# main.net
KiCad netlist of a schematic drawn in EAGLE
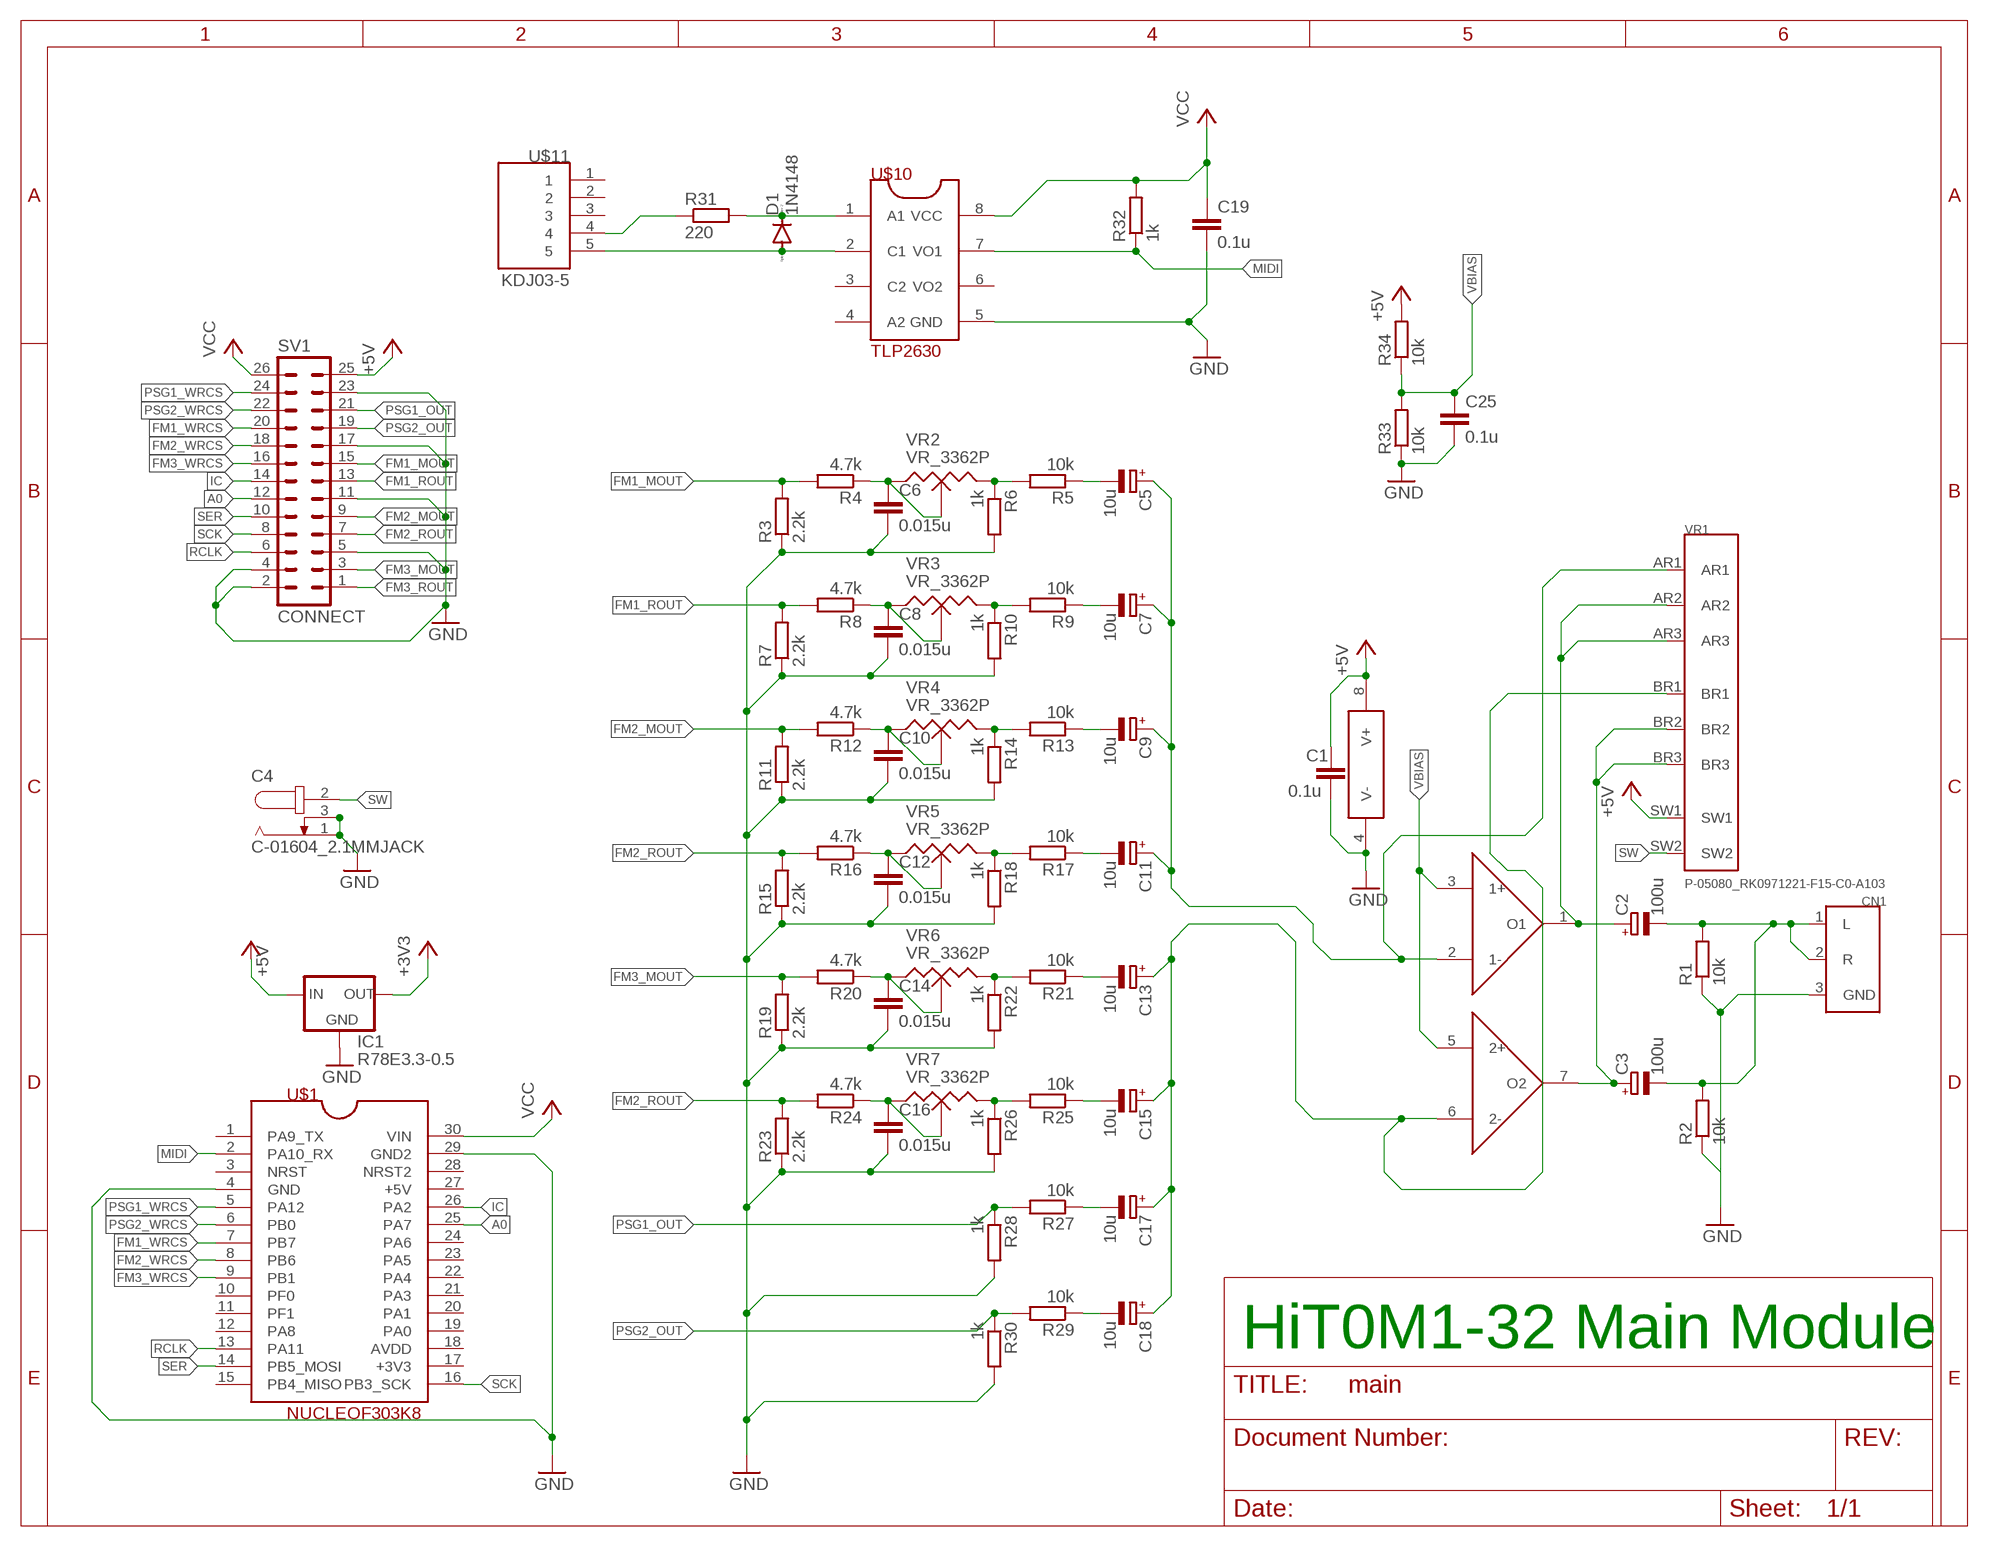
[diagram p0: schematic, sheet 1]

(export (version "E")
  (design (tool "Eeschema 10.0.6"))
  (components
    (comp (ref "C1")
      (value "0.1u")
      (footprint "eagle-import:C025-025X050")
      (libsource (lib "eagle-import") (part "C-EU025-025X050"))
    )
    (comp (ref "C2")
      (value "100u")
      (footprint "eagle-import:E2,5-6E")
      (libsource (lib "eagle-import") (part "CPOL-EUE2,5-6E"))
    )
    (comp (ref "C3")
      (value "100u")
      (footprint "eagle-import:E2,5-6E")
      (libsource (lib "eagle-import") (part "CPOL-EUE2,5-6E"))
    )
    (comp (ref "C4")
      (value "C-01604_2.1MMJACK")
      (footprint "eagle-import:2.1MMJACK")
      (libsource (lib "eagle-import") (part "C-01604_2.1MMJACK"))
    )
    (comp (ref "C5")
      (value "10u")
      (footprint "eagle-import:E2,5-6E")
      (libsource (lib "eagle-import") (part "CPOL-EUE2,5-6E"))
    )
    (comp (ref "C6")
      (value "0.015u")
      (footprint "eagle-import:C050-025X075")
      (libsource (lib "eagle-import") (part "C-EU050-025X075"))
    )
    (comp (ref "C7")
      (value "10u")
      (footprint "eagle-import:E2,5-6E")
      (libsource (lib "eagle-import") (part "CPOL-EUE2,5-6E"))
    )
    (comp (ref "C8")
      (value "0.015u")
      (footprint "eagle-import:C050-025X075")
      (libsource (lib "eagle-import") (part "C-EU050-025X075"))
    )
    (comp (ref "C9")
      (value "10u")
      (footprint "eagle-import:E2,5-6E")
      (libsource (lib "eagle-import") (part "CPOL-EUE2,5-6E"))
    )
    (comp (ref "C10")
      (value "0.015u")
      (footprint "eagle-import:C050-025X075")
      (libsource (lib "eagle-import") (part "C-EU050-025X075"))
    )
    (comp (ref "C11")
      (value "10u")
      (footprint "eagle-import:E2,5-6E")
      (libsource (lib "eagle-import") (part "CPOL-EUE2,5-6E"))
    )
    (comp (ref "C12")
      (value "0.015u")
      (footprint "eagle-import:C050-025X075")
      (libsource (lib "eagle-import") (part "C-EU050-025X075"))
    )
    (comp (ref "C13")
      (value "10u")
      (footprint "eagle-import:E2,5-6E")
      (libsource (lib "eagle-import") (part "CPOL-EUE2,5-6E"))
    )
    (comp (ref "C14")
      (value "0.015u")
      (footprint "eagle-import:C050-025X075")
      (libsource (lib "eagle-import") (part "C-EU050-025X075"))
    )
    (comp (ref "C15")
      (value "10u")
      (footprint "eagle-import:E2,5-6E")
      (libsource (lib "eagle-import") (part "CPOL-EUE2,5-6E"))
    )
    (comp (ref "C16")
      (value "0.015u")
      (footprint "eagle-import:C050-025X075")
      (libsource (lib "eagle-import") (part "C-EU050-025X075"))
    )
    (comp (ref "C17")
      (value "10u")
      (footprint "eagle-import:E2,5-6E")
      (libsource (lib "eagle-import") (part "CPOL-EUE2,5-6E"))
    )
    (comp (ref "C18")
      (value "10u")
      (footprint "eagle-import:E2,5-6E")
      (libsource (lib "eagle-import") (part "CPOL-EUE2,5-6E"))
    )
    (comp (ref "C19")
      (value "0.1u")
      (footprint "eagle-import:C025-025X050")
      (libsource (lib "eagle-import") (part "C-EU025-025X050"))
    )
    (comp (ref "C25")
      (value "0.1u")
      (footprint "eagle-import:C025-025X050")
      (libsource (lib "eagle-import") (part "C-EU025-025X050"))
    )
    (comp (ref "CN1")
      (value "C-08958_MJ-352W-0")
      (footprint "eagle-import:MJ-352W-0")
      (libsource (lib "eagle-import") (part "C-08958_MJ-352W-0"))
    )
    (comp (ref "D1")
      (value "1N4148")
      (footprint "eagle-import:DO35-7")
      (libsource (lib "eagle-import") (part "1N4148DO35-7"))
    )
    (comp (ref "IC1")
      (value "R78E3.3-0.5")
      (footprint "eagle-import:78XXS")
      (libsource (lib "eagle-import") (part "78XXS"))
    )
    (comp (ref "R1")
      (value "10k")
      (footprint "eagle-import:0204_7")
      (libsource (lib "eagle-import") (part "R-EU_0204/7"))
    )
    (comp (ref "R2")
      (value "10k")
      (footprint "eagle-import:0204_7")
      (libsource (lib "eagle-import") (part "R-EU_0204/7"))
    )
    (comp (ref "R3")
      (value "2.2k")
      (footprint "eagle-import:0204_7")
      (libsource (lib "eagle-import") (part "R-EU_0204/7"))
    )
    (comp (ref "R4")
      (value "4.7k")
      (footprint "eagle-import:0204_7")
      (libsource (lib "eagle-import") (part "R-EU_0204/7"))
    )
    (comp (ref "R5")
      (value "10k")
      (footprint "eagle-import:0204_7")
      (libsource (lib "eagle-import") (part "R-EU_0204/7"))
    )
    (comp (ref "R6")
      (value "1k")
      (footprint "eagle-import:0204_7")
      (libsource (lib "eagle-import") (part "R-EU_0204/7"))
    )
    (comp (ref "R7")
      (value "2.2k")
      (footprint "eagle-import:0204_7")
      (libsource (lib "eagle-import") (part "R-EU_0204/7"))
    )
    (comp (ref "R8")
      (value "4.7k")
      (footprint "eagle-import:0204_7")
      (libsource (lib "eagle-import") (part "R-EU_0204/7"))
    )
    (comp (ref "R9")
      (value "10k")
      (footprint "eagle-import:0204_7")
      (libsource (lib "eagle-import") (part "R-EU_0204/7"))
    )
    (comp (ref "R10")
      (value "1k")
      (footprint "eagle-import:0204_7")
      (libsource (lib "eagle-import") (part "R-EU_0204/7"))
    )
    (comp (ref "R11")
      (value "2.2k")
      (footprint "eagle-import:0204_7")
      (libsource (lib "eagle-import") (part "R-EU_0204/7"))
    )
    (comp (ref "R12")
      (value "4.7k")
      (footprint "eagle-import:0204_7")
      (libsource (lib "eagle-import") (part "R-EU_0204/7"))
    )
    (comp (ref "R13")
      (value "10k")
      (footprint "eagle-import:0204_7")
      (libsource (lib "eagle-import") (part "R-EU_0204/7"))
    )
    (comp (ref "R14")
      (value "1k")
      (footprint "eagle-import:0204_7")
      (libsource (lib "eagle-import") (part "R-EU_0204/7"))
    )
    (comp (ref "R15")
      (value "2.2k")
      (footprint "eagle-import:0204_7")
      (libsource (lib "eagle-import") (part "R-EU_0204/7"))
    )
    (comp (ref "R16")
      (value "4.7k")
      (footprint "eagle-import:0204_7")
      (libsource (lib "eagle-import") (part "R-EU_0204/7"))
    )
    (comp (ref "R17")
      (value "10k")
      (footprint "eagle-import:0204_7")
      (libsource (lib "eagle-import") (part "R-EU_0204/7"))
    )
    (comp (ref "R18")
      (value "1k")
      (footprint "eagle-import:0204_7")
      (libsource (lib "eagle-import") (part "R-EU_0204/7"))
    )
    (comp (ref "R19")
      (value "2.2k")
      (footprint "eagle-import:0204_7")
      (libsource (lib "eagle-import") (part "R-EU_0204/7"))
    )
    (comp (ref "R20")
      (value "4.7k")
      (footprint "eagle-import:0204_7")
      (libsource (lib "eagle-import") (part "R-EU_0204/7"))
    )
    (comp (ref "R21")
      (value "10k")
      (footprint "eagle-import:0204_7")
      (libsource (lib "eagle-import") (part "R-EU_0204/7"))
    )
    (comp (ref "R22")
      (value "1k")
      (footprint "eagle-import:0204_7")
      (libsource (lib "eagle-import") (part "R-EU_0204/7"))
    )
    (comp (ref "R23")
      (value "2.2k")
      (footprint "eagle-import:0204_7")
      (libsource (lib "eagle-import") (part "R-EU_0204/7"))
    )
    (comp (ref "R24")
      (value "4.7k")
      (footprint "eagle-import:0204_7")
      (libsource (lib "eagle-import") (part "R-EU_0204/7"))
    )
    (comp (ref "R25")
      (value "10k")
      (footprint "eagle-import:0204_7")
      (libsource (lib "eagle-import") (part "R-EU_0204/7"))
    )
    (comp (ref "R26")
      (value "1k")
      (footprint "eagle-import:0204_7")
      (libsource (lib "eagle-import") (part "R-EU_0204/7"))
    )
    (comp (ref "R27")
      (value "10k")
      (footprint "eagle-import:0204_7")
      (libsource (lib "eagle-import") (part "R-EU_0204/7"))
    )
    (comp (ref "R28")
      (value "1k")
      (footprint "eagle-import:0204_7")
      (libsource (lib "eagle-import") (part "R-EU_0204/7"))
    )
    (comp (ref "R29")
      (value "10k")
      (footprint "eagle-import:0204_7")
      (libsource (lib "eagle-import") (part "R-EU_0204/7"))
    )
    (comp (ref "R30")
      (value "1k")
      (footprint "eagle-import:0204_7")
      (libsource (lib "eagle-import") (part "R-EU_0204/7"))
    )
    (comp (ref "R31")
      (value "220")
      (footprint "eagle-import:0204_7")
      (libsource (lib "eagle-import") (part "R-EU_0204/7"))
    )
    (comp (ref "R32")
      (value "1k")
      (footprint "eagle-import:0204_7")
      (libsource (lib "eagle-import") (part "R-EU_0204/7"))
    )
    (comp (ref "R33")
      (value "10k")
      (footprint "eagle-import:0204_7")
      (libsource (lib "eagle-import") (part "R-EU_0204/7"))
    )
    (comp (ref "R34")
      (value "10k")
      (footprint "eagle-import:0204_7")
      (libsource (lib "eagle-import") (part "R-EU_0204/7"))
    )
    (comp (ref "SV1")
      (value "CONNECT")
      (footprint "eagle-import:MA13-2")
      (libsource (lib "eagle-import") (part "MA13-2"))
    )
    (comp (ref "U$1")
      (value "NUCLEOF303K8")
      (footprint "eagle-import:NUCLEOF303K8")
      (libsource (lib "eagle-import") (part "NUCLEOF303K8"))
    )
    (comp (ref "U$2")
      (value "NJM2114")
      (footprint "eagle-import:DIL08")
      (libsource (lib "eagle-import") (part "NJM2114"))
    )
    (comp (ref "U$10")
      (value "TLP2630")
      (footprint "eagle-import:DIL08")
      (libsource (lib "eagle-import") (part "TLP2630TLP2630"))
    )
    (comp (ref "U$11")
      (value "KDJ03-5")
      (footprint "eagle-import:KDJ03-5")
      (libsource (lib "eagle-import") (part "KDJ03-5"))
    )
    (comp (ref "VR1")
      (value "P-05080_RK0971221-F15-C0-A103")
      (footprint "eagle-import:RK0971221-F15-C0-A103")
      (libsource (lib "eagle-import") (part "P-05080_RK0971221-F15-C0-A103"))
    )
    (comp (ref "VR2")
      (value "VR_3362P")
      (footprint "eagle-import:VR_3362P")
      (libsource (lib "eagle-import") (part "P-03277_VR_3362P"))
    )
    (comp (ref "VR3")
      (value "VR_3362P")
      (footprint "eagle-import:VR_3362P")
      (libsource (lib "eagle-import") (part "P-03277_VR_3362P"))
    )
    (comp (ref "VR4")
      (value "VR_3362P")
      (footprint "eagle-import:VR_3362P")
      (libsource (lib "eagle-import") (part "P-03277_VR_3362P"))
    )
    (comp (ref "VR5")
      (value "VR_3362P")
      (footprint "eagle-import:VR_3362P")
      (libsource (lib "eagle-import") (part "P-03277_VR_3362P"))
    )
    (comp (ref "VR6")
      (value "VR_3362P")
      (footprint "eagle-import:VR_3362P")
      (libsource (lib "eagle-import") (part "P-03277_VR_3362P"))
    )
    (comp (ref "VR7")
      (value "VR_3362P")
      (footprint "eagle-import:VR_3362P")
      (libsource (lib "eagle-import") (part "P-03277_VR_3362P"))
    )
  )
  (nets
    (net (code "1") (name "+3V3") (class "Default")
      (node (ref "IC1") (pin "OUT") (pinfunction "OUT_OUT") (pintype "passive"))
    )
    (net (code "2") (name "+5V") (class "Default")
      (node (ref "C1") (pin "1") (pinfunction "1_1") (pintype "passive"))
      (node (ref "IC1") (pin "IN") (pinfunction "IN_IN") (pintype "input"))
      (node (ref "R34") (pin "2") (pinfunction "2_2") (pintype "passive"))
      (node (ref "SV1") (pin "25") (pinfunction "25_25") (pintype "passive"))
      (node (ref "U$2") (pin "8") (pinfunction "V+_8") (pintype "bidirectional"))
      (node (ref "VR1") (pin "SW1") (pinfunction "SW1_SW1") (pintype "bidirectional"))
    )
    (net (code "3") (name "A0") (class "Default")
      (node (ref "SV1") (pin "12") (pinfunction "12_12") (pintype "passive"))
      (node (ref "U$1") (pin "25") (pinfunction "PA7_25") (pintype "bidirectional"))
    )
    (net (code "4") (name "FM1_MOUT") (class "Default")
      (node (ref "R3") (pin "2") (pinfunction "2_2") (pintype "passive"))
      (node (ref "R4") (pin "2") (pinfunction "2_2") (pintype "passive"))
      (node (ref "SV1") (pin "15") (pinfunction "15_15") (pintype "passive"))
    )
    (net (code "5") (name "FM1_ROUT") (class "Default")
      (node (ref "R7") (pin "2") (pinfunction "2_2") (pintype "passive"))
      (node (ref "R8") (pin "2") (pinfunction "2_2") (pintype "passive"))
      (node (ref "SV1") (pin "13") (pinfunction "13_13") (pintype "passive"))
    )
    (net (code "6") (name "FM1_WRCS") (class "Default")
      (node (ref "SV1") (pin "20") (pinfunction "20_20") (pintype "passive"))
      (node (ref "U$1") (pin "7") (pinfunction "PB7_7") (pintype "bidirectional"))
    )
    (net (code "7") (name "FM2_MOUT") (class "Default")
      (node (ref "R11") (pin "2") (pinfunction "2_2") (pintype "passive"))
      (node (ref "R12") (pin "2") (pinfunction "2_2") (pintype "passive"))
      (node (ref "SV1") (pin "9") (pinfunction "9_9") (pintype "passive"))
    )
    (net (code "8") (name "FM2_ROUT") (class "Default")
      (node (ref "R15") (pin "2") (pinfunction "2_2") (pintype "passive"))
      (node (ref "R16") (pin "2") (pinfunction "2_2") (pintype "passive"))
      (node (ref "R23") (pin "2") (pinfunction "2_2") (pintype "passive"))
      (node (ref "R24") (pin "2") (pinfunction "2_2") (pintype "passive"))
      (node (ref "SV1") (pin "7") (pinfunction "7_7") (pintype "passive"))
    )
    (net (code "9") (name "FM2_WRCS") (class "Default")
      (node (ref "SV1") (pin "18") (pinfunction "18_18") (pintype "passive"))
      (node (ref "U$1") (pin "8") (pinfunction "PB6_8") (pintype "bidirectional"))
    )
    (net (code "10") (name "FM3_MOUT") (class "Default")
      (node (ref "R19") (pin "2") (pinfunction "2_2") (pintype "passive"))
      (node (ref "R20") (pin "2") (pinfunction "2_2") (pintype "passive"))
      (node (ref "SV1") (pin "3") (pinfunction "3_3") (pintype "passive"))
    )
    (net (code "11") (name "FM3_ROUT") (class "Default")
      (node (ref "SV1") (pin "1") (pinfunction "1_1") (pintype "passive"))
    )
    (net (code "12") (name "FM3_WRCS") (class "Default")
      (node (ref "SV1") (pin "16") (pinfunction "16_16") (pintype "passive"))
      (node (ref "U$1") (pin "9") (pinfunction "PB1_9") (pintype "bidirectional"))
    )
    (net (code "13") (name "GND") (class "Default")
      (node (ref "C1") (pin "2") (pinfunction "2_2") (pintype "passive"))
      (node (ref "C10") (pin "2") (pinfunction "2_2") (pintype "passive"))
      (node (ref "C12") (pin "2") (pinfunction "2_2") (pintype "passive"))
      (node (ref "C14") (pin "2") (pinfunction "2_2") (pintype "passive"))
      (node (ref "C16") (pin "2") (pinfunction "2_2") (pintype "passive"))
      (node (ref "C19") (pin "2") (pinfunction "2_2") (pintype "passive"))
      (node (ref "C25") (pin "2") (pinfunction "2_2") (pintype "passive"))
      (node (ref "C4") (pin "1") (pinfunction "GND_1") (pintype "passive"))
      (node (ref "C4") (pin "3") (pinfunction "S_3") (pintype "passive"))
      (node (ref "C6") (pin "2") (pinfunction "2_2") (pintype "passive"))
      (node (ref "C8") (pin "2") (pinfunction "2_2") (pintype "passive"))
      (node (ref "CN1") (pin "3") (pinfunction "GND_3") (pintype "bidirectional"))
      (node (ref "IC1") (pin "GND") (pinfunction "GND_GND") (pintype "input"))
      (node (ref "R1") (pin "1") (pinfunction "1_1") (pintype "passive"))
      (node (ref "R10") (pin "2") (pinfunction "2_2") (pintype "passive"))
      (node (ref "R11") (pin "1") (pinfunction "1_1") (pintype "passive"))
      (node (ref "R14") (pin "2") (pinfunction "2_2") (pintype "passive"))
      (node (ref "R15") (pin "1") (pinfunction "1_1") (pintype "passive"))
      (node (ref "R18") (pin "2") (pinfunction "2_2") (pintype "passive"))
      (node (ref "R19") (pin "1") (pinfunction "1_1") (pintype "passive"))
      (node (ref "R22") (pin "2") (pinfunction "2_2") (pintype "passive"))
      (node (ref "R23") (pin "1") (pinfunction "1_1") (pintype "passive"))
      (node (ref "R26") (pin "2") (pinfunction "2_2") (pintype "passive"))
      (node (ref "R28") (pin "2") (pinfunction "2_2") (pintype "passive"))
      (node (ref "R3") (pin "1") (pinfunction "1_1") (pintype "passive"))
      (node (ref "R30") (pin "2") (pinfunction "2_2") (pintype "passive"))
      (node (ref "R33") (pin "1") (pinfunction "1_1") (pintype "passive"))
      (node (ref "R6") (pin "2") (pinfunction "2_2") (pintype "passive"))
      (node (ref "R7") (pin "1") (pinfunction "1_1") (pintype "passive"))
      (node (ref "SV1") (pin "11") (pinfunction "11_11") (pintype "passive"))
      (node (ref "SV1") (pin "17") (pinfunction "17_17") (pintype "passive"))
      (node (ref "SV1") (pin "2") (pinfunction "2_2") (pintype "passive"))
      (node (ref "SV1") (pin "23") (pinfunction "23_23") (pintype "passive"))
      (node (ref "SV1") (pin "4") (pinfunction "4_4") (pintype "passive"))
      (node (ref "SV1") (pin "5") (pinfunction "5_5") (pintype "passive"))
      (node (ref "U$1") (pin "29") (pinfunction "GND2_29") (pintype "bidirectional"))
      (node (ref "U$1") (pin "4") (pinfunction "GND_4") (pintype "bidirectional"))
      (node (ref "U$10") (pin "5") (pinfunction "GND_5") (pintype "bidirectional"))
      (node (ref "U$2") (pin "4") (pinfunction "V-_4") (pintype "bidirectional"))
    )
    (net (code "14") (name "IC") (class "Default")
      (node (ref "SV1") (pin "14") (pinfunction "14_14") (pintype "passive"))
      (node (ref "U$1") (pin "26") (pinfunction "PA2_26") (pintype "bidirectional"))
    )
    (net (code "15") (name "MIDI") (class "Default")
      (node (ref "R32") (pin "1") (pinfunction "1_1") (pintype "passive"))
      (node (ref "U$1") (pin "2") (pinfunction "PA10_RX_2") (pintype "bidirectional"))
      (node (ref "U$10") (pin "7") (pinfunction "VO1_7") (pintype "bidirectional"))
    )
    (net (code "16") (name "Net-(C5-Pad-)") (class "Default")
      (node (ref "C5") (pin "-") (pinfunction "-_-") (pintype "passive"))
      (node (ref "R5") (pin "1") (pinfunction "1_1") (pintype "passive"))
    )
    (net (code "17") (name "Net-(C6-Pad1)") (class "Default")
      (node (ref "C6") (pin "1") (pinfunction "1_1") (pintype "passive"))
      (node (ref "R4") (pin "1") (pinfunction "1_1") (pintype "passive"))
      (node (ref "VR2") (pin "1") (pinfunction "1_1") (pintype "bidirectional"))
      (node (ref "VR2") (pin "2") (pinfunction "2_2") (pintype "bidirectional"))
    )
    (net (code "18") (name "Net-(C7-Pad-)") (class "Default")
      (node (ref "C7") (pin "-") (pinfunction "-_-") (pintype "passive"))
      (node (ref "R9") (pin "1") (pinfunction "1_1") (pintype "passive"))
    )
    (net (code "19") (name "Net-(C8-Pad1)") (class "Default")
      (node (ref "C8") (pin "1") (pinfunction "1_1") (pintype "passive"))
      (node (ref "R8") (pin "1") (pinfunction "1_1") (pintype "passive"))
      (node (ref "VR3") (pin "1") (pinfunction "1_1") (pintype "bidirectional"))
      (node (ref "VR3") (pin "2") (pinfunction "2_2") (pintype "bidirectional"))
    )
    (net (code "20") (name "Net-(C9-Pad-)") (class "Default")
      (node (ref "C9") (pin "-") (pinfunction "-_-") (pintype "passive"))
      (node (ref "R13") (pin "1") (pinfunction "1_1") (pintype "passive"))
    )
    (net (code "21") (name "Net-(C10-Pad1)") (class "Default")
      (node (ref "C10") (pin "1") (pinfunction "1_1") (pintype "passive"))
      (node (ref "R12") (pin "1") (pinfunction "1_1") (pintype "passive"))
      (node (ref "VR4") (pin "1") (pinfunction "1_1") (pintype "bidirectional"))
      (node (ref "VR4") (pin "2") (pinfunction "2_2") (pintype "bidirectional"))
    )
    (net (code "22") (name "Net-(C11-Pad-)") (class "Default")
      (node (ref "C11") (pin "-") (pinfunction "-_-") (pintype "passive"))
      (node (ref "R17") (pin "1") (pinfunction "1_1") (pintype "passive"))
    )
    (net (code "23") (name "Net-(C12-Pad1)") (class "Default")
      (node (ref "C12") (pin "1") (pinfunction "1_1") (pintype "passive"))
      (node (ref "R16") (pin "1") (pinfunction "1_1") (pintype "passive"))
      (node (ref "VR5") (pin "1") (pinfunction "1_1") (pintype "bidirectional"))
      (node (ref "VR5") (pin "2") (pinfunction "2_2") (pintype "bidirectional"))
    )
    (net (code "24") (name "Net-(C13-Pad-)") (class "Default")
      (node (ref "C13") (pin "-") (pinfunction "-_-") (pintype "passive"))
      (node (ref "R21") (pin "1") (pinfunction "1_1") (pintype "passive"))
    )
    (net (code "25") (name "Net-(C14-Pad1)") (class "Default")
      (node (ref "C14") (pin "1") (pinfunction "1_1") (pintype "passive"))
      (node (ref "R20") (pin "1") (pinfunction "1_1") (pintype "passive"))
      (node (ref "VR6") (pin "1") (pinfunction "1_1") (pintype "bidirectional"))
      (node (ref "VR6") (pin "2") (pinfunction "2_2") (pintype "bidirectional"))
    )
    (net (code "26") (name "Net-(C15-Pad-)") (class "Default")
      (node (ref "C15") (pin "-") (pinfunction "-_-") (pintype "passive"))
      (node (ref "R25") (pin "1") (pinfunction "1_1") (pintype "passive"))
    )
    (net (code "27") (name "Net-(C16-Pad1)") (class "Default")
      (node (ref "C16") (pin "1") (pinfunction "1_1") (pintype "passive"))
      (node (ref "R24") (pin "1") (pinfunction "1_1") (pintype "passive"))
      (node (ref "VR7") (pin "1") (pinfunction "1_1") (pintype "bidirectional"))
      (node (ref "VR7") (pin "2") (pinfunction "2_2") (pintype "bidirectional"))
    )
    (net (code "28") (name "Net-(C17-Pad-)") (class "Default")
      (node (ref "C17") (pin "-") (pinfunction "-_-") (pintype "passive"))
      (node (ref "R27") (pin "1") (pinfunction "1_1") (pintype "passive"))
    )
    (net (code "29") (name "Net-(C18-Pad-)") (class "Default")
      (node (ref "C18") (pin "-") (pinfunction "-_-") (pintype "passive"))
      (node (ref "R29") (pin "1") (pinfunction "1_1") (pintype "passive"))
    )
    (net (code "30") (name "Net-(CN1-L)") (class "Default")
      (node (ref "C2") (pin "-") (pinfunction "-_-") (pintype "passive"))
      (node (ref "C3") (pin "-") (pinfunction "-_-") (pintype "passive"))
      (node (ref "CN1") (pin "1") (pinfunction "L_1") (pintype "bidirectional"))
      (node (ref "CN1") (pin "2") (pinfunction "R_2") (pintype "bidirectional"))
      (node (ref "R1") (pin "2") (pinfunction "2_2") (pintype "passive"))
      (node (ref "R2") (pin "2") (pinfunction "2_2") (pintype "passive"))
    )
    (net (code "31") (name "Net-(R5-Pad2)") (class "Default")
      (node (ref "R5") (pin "2") (pinfunction "2_2") (pintype "passive"))
      (node (ref "R6") (pin "1") (pinfunction "1_1") (pintype "passive"))
      (node (ref "VR2") (pin "3") (pinfunction "3_3") (pintype "bidirectional"))
    )
    (net (code "32") (name "Net-(R10-Pad1)") (class "Default")
      (node (ref "R10") (pin "1") (pinfunction "1_1") (pintype "passive"))
      (node (ref "R9") (pin "2") (pinfunction "2_2") (pintype "passive"))
      (node (ref "VR3") (pin "3") (pinfunction "3_3") (pintype "bidirectional"))
    )
    (net (code "33") (name "Net-(R13-Pad2)") (class "Default")
      (node (ref "R13") (pin "2") (pinfunction "2_2") (pintype "passive"))
      (node (ref "R14") (pin "1") (pinfunction "1_1") (pintype "passive"))
      (node (ref "VR4") (pin "3") (pinfunction "3_3") (pintype "bidirectional"))
    )
    (net (code "34") (name "Net-(R17-Pad2)") (class "Default")
      (node (ref "R17") (pin "2") (pinfunction "2_2") (pintype "passive"))
      (node (ref "R18") (pin "1") (pinfunction "1_1") (pintype "passive"))
      (node (ref "VR5") (pin "3") (pinfunction "3_3") (pintype "bidirectional"))
    )
    (net (code "35") (name "Net-(R21-Pad2)") (class "Default")
      (node (ref "R21") (pin "2") (pinfunction "2_2") (pintype "passive"))
      (node (ref "R22") (pin "1") (pinfunction "1_1") (pintype "passive"))
      (node (ref "VR6") (pin "3") (pinfunction "3_3") (pintype "bidirectional"))
    )
    (net (code "36") (name "Net-(R25-Pad2)") (class "Default")
      (node (ref "R25") (pin "2") (pinfunction "2_2") (pintype "passive"))
      (node (ref "R26") (pin "1") (pinfunction "1_1") (pintype "passive"))
      (node (ref "VR7") (pin "3") (pinfunction "3_3") (pintype "bidirectional"))
    )
    (net (code "37") (name "Net-(R31-Pad1)") (class "Default")
      (node (ref "R31") (pin "1") (pinfunction "1_1") (pintype "passive"))
      (node (ref "U$11") (pin "4") (pinfunction "4_4") (pintype "bidirectional"))
    )
    (net (code "38") (name "Net-(U$2-1-)") (class "Default")
      (node (ref "C11") (pin "+") (pinfunction "+_+") (pintype "passive"))
      (node (ref "C5") (pin "+") (pinfunction "+_+") (pintype "passive"))
      (node (ref "C7") (pin "+") (pinfunction "+_+") (pintype "passive"))
      (node (ref "C9") (pin "+") (pinfunction "+_+") (pintype "passive"))
      (node (ref "U$2") (pin "2") (pinfunction "1-_2") (pintype "bidirectional"))
      (node (ref "VR1") (pin "AR1") (pinfunction "AR1_AR1") (pintype "bidirectional"))
    )
    (net (code "39") (name "Net-(U$2-2-)") (class "Default")
      (node (ref "C13") (pin "+") (pinfunction "+_+") (pintype "passive"))
      (node (ref "C15") (pin "+") (pinfunction "+_+") (pintype "passive"))
      (node (ref "C17") (pin "+") (pinfunction "+_+") (pintype "passive"))
      (node (ref "C18") (pin "+") (pinfunction "+_+") (pintype "passive"))
      (node (ref "U$2") (pin "6") (pinfunction "2-_6") (pintype "bidirectional"))
      (node (ref "VR1") (pin "BR1") (pinfunction "BR1_BR1") (pintype "bidirectional"))
    )
    (net (code "40") (name "Net-(U$2-O1)") (class "Default")
      (node (ref "C2") (pin "+") (pinfunction "+_+") (pintype "passive"))
      (node (ref "U$2") (pin "1") (pinfunction "O1_1") (pintype "bidirectional"))
      (node (ref "VR1") (pin "AR2") (pinfunction "AR2_AR2") (pintype "bidirectional"))
      (node (ref "VR1") (pin "AR3") (pinfunction "AR3_AR3") (pintype "bidirectional"))
    )
    (net (code "41") (name "Net-(U$2-O2)") (class "Default")
      (node (ref "C3") (pin "+") (pinfunction "+_+") (pintype "passive"))
      (node (ref "U$2") (pin "7") (pinfunction "O2_7") (pintype "bidirectional"))
      (node (ref "VR1") (pin "BR2") (pinfunction "BR2_BR2") (pintype "bidirectional"))
      (node (ref "VR1") (pin "BR3") (pinfunction "BR3_BR3") (pintype "bidirectional"))
    )
    (net (code "42") (name "Net-(U$10-A1)") (class "Default")
      (node (ref "D1") (pin "C") (pinfunction "C_C") (pintype "passive"))
      (node (ref "R31") (pin "2") (pinfunction "2_2") (pintype "passive"))
      (node (ref "U$10") (pin "1") (pinfunction "A1_1") (pintype "bidirectional"))
    )
    (net (code "43") (name "Net-(U$10-C1)") (class "Default")
      (node (ref "D1") (pin "A") (pinfunction "A_A") (pintype "passive"))
      (node (ref "U$10") (pin "2") (pinfunction "C1_2") (pintype "bidirectional"))
      (node (ref "U$11") (pin "5") (pinfunction "5_5") (pintype "bidirectional"))
    )
    (net (code "44") (name "PSG1_OUT") (class "Default")
      (node (ref "R27") (pin "2") (pinfunction "2_2") (pintype "passive"))
      (node (ref "R28") (pin "1") (pinfunction "1_1") (pintype "passive"))
      (node (ref "SV1") (pin "21") (pinfunction "21_21") (pintype "passive"))
    )
    (net (code "45") (name "PSG1_WRCS") (class "Default")
      (node (ref "SV1") (pin "24") (pinfunction "24_24") (pintype "passive"))
      (node (ref "U$1") (pin "5") (pinfunction "PA12_5") (pintype "bidirectional"))
    )
    (net (code "46") (name "PSG2_OUT") (class "Default")
      (node (ref "R29") (pin "2") (pinfunction "2_2") (pintype "passive"))
      (node (ref "R30") (pin "1") (pinfunction "1_1") (pintype "passive"))
      (node (ref "SV1") (pin "19") (pinfunction "19_19") (pintype "passive"))
    )
    (net (code "47") (name "PSG2_WRCS") (class "Default")
      (node (ref "SV1") (pin "22") (pinfunction "22_22") (pintype "passive"))
      (node (ref "U$1") (pin "6") (pinfunction "PB0_6") (pintype "bidirectional"))
    )
    (net (code "48") (name "RCLK") (class "Default")
      (node (ref "SV1") (pin "6") (pinfunction "6_6") (pintype "passive"))
      (node (ref "U$1") (pin "13") (pinfunction "PA11_13") (pintype "bidirectional"))
    )
    (net (code "49") (name "SCK") (class "Default")
      (node (ref "SV1") (pin "8") (pinfunction "8_8") (pintype "passive"))
      (node (ref "U$1") (pin "16") (pinfunction "PB3_SCK_16") (pintype "bidirectional"))
    )
    (net (code "50") (name "SER") (class "Default")
      (node (ref "SV1") (pin "10") (pinfunction "10_10") (pintype "passive"))
      (node (ref "U$1") (pin "14") (pinfunction "PB5_MOSI_14") (pintype "bidirectional"))
    )
    (net (code "51") (name "SW") (class "Default")
      (node (ref "C4") (pin "2") (pinfunction "VCC_2") (pintype "passive"))
      (node (ref "VR1") (pin "SW2") (pinfunction "SW2_SW2") (pintype "bidirectional"))
    )
    (net (code "52") (name "VBIAS") (class "Default")
      (node (ref "C25") (pin "1") (pinfunction "1_1") (pintype "passive"))
      (node (ref "R33") (pin "2") (pinfunction "2_2") (pintype "passive"))
      (node (ref "R34") (pin "1") (pinfunction "1_1") (pintype "passive"))
      (node (ref "U$2") (pin "3") (pinfunction "1+_3") (pintype "bidirectional"))
      (node (ref "U$2") (pin "5") (pinfunction "2+_5") (pintype "bidirectional"))
    )
    (net (code "53") (name "VCC") (class "Default")
      (node (ref "C19") (pin "1") (pinfunction "1_1") (pintype "passive"))
      (node (ref "R32") (pin "2") (pinfunction "2_2") (pintype "passive"))
      (node (ref "SV1") (pin "26") (pinfunction "26_26") (pintype "passive"))
      (node (ref "U$1") (pin "30") (pinfunction "VIN_30") (pintype "bidirectional"))
      (node (ref "U$10") (pin "8") (pinfunction "VCC_8") (pintype "bidirectional"))
    )
    (net (code "54") (name "unconnected-(R2-Pad1)") (class "Default")
      (node (ref "R2") (pin "1") (pinfunction "1_1") (pintype "passive"))
    )
    (net (code "55") (name "unconnected-(U$1-+3V3-Pad17)") (class "Default")
      (node (ref "U$1") (pin "17") (pinfunction "+3V3_17") (pintype "bidirectional"))
    )
    (net (code "56") (name "unconnected-(U$1-+5V-Pad27)") (class "Default")
      (node (ref "U$1") (pin "27") (pinfunction "+5V_27") (pintype "bidirectional"))
    )
    (net (code "57") (name "unconnected-(U$1-AVDD-Pad18)") (class "Default")
      (node (ref "U$1") (pin "18") (pinfunction "AVDD_18") (pintype "bidirectional"))
    )
    (net (code "58") (name "unconnected-(U$1-NRST-Pad3)") (class "Default")
      (node (ref "U$1") (pin "3") (pinfunction "NRST_3") (pintype "bidirectional"))
    )
    (net (code "59") (name "unconnected-(U$1-NRST2-Pad28)") (class "Default")
      (node (ref "U$1") (pin "28") (pinfunction "NRST2_28") (pintype "bidirectional"))
    )
    (net (code "60") (name "unconnected-(U$1-PA0-Pad19)") (class "Default")
      (node (ref "U$1") (pin "19") (pinfunction "PA0_19") (pintype "bidirectional"))
    )
    (net (code "61") (name "unconnected-(U$1-PA1-Pad20)") (class "Default")
      (node (ref "U$1") (pin "20") (pinfunction "PA1_20") (pintype "bidirectional"))
    )
    (net (code "62") (name "unconnected-(U$1-PA3-Pad21)") (class "Default")
      (node (ref "U$1") (pin "21") (pinfunction "PA3_21") (pintype "bidirectional"))
    )
    (net (code "63") (name "unconnected-(U$1-PA4-Pad22)") (class "Default")
      (node (ref "U$1") (pin "22") (pinfunction "PA4_22") (pintype "bidirectional"))
    )
    (net (code "64") (name "unconnected-(U$1-PA5-Pad23)") (class "Default")
      (node (ref "U$1") (pin "23") (pinfunction "PA5_23") (pintype "bidirectional"))
    )
    (net (code "65") (name "unconnected-(U$1-PA6-Pad24)") (class "Default")
      (node (ref "U$1") (pin "24") (pinfunction "PA6_24") (pintype "bidirectional"))
    )
    (net (code "66") (name "unconnected-(U$1-PA8-Pad12)") (class "Default")
      (node (ref "U$1") (pin "12") (pinfunction "PA8_12") (pintype "bidirectional"))
    )
    (net (code "67") (name "unconnected-(U$1-PA9_TX-Pad1)") (class "Default")
      (node (ref "U$1") (pin "1") (pinfunction "PA9_TX_1") (pintype "bidirectional"))
    )
    (net (code "68") (name "unconnected-(U$1-PB4_MISO-Pad15)") (class "Default")
      (node (ref "U$1") (pin "15") (pinfunction "PB4_MISO_15") (pintype "bidirectional"))
    )
    (net (code "69") (name "unconnected-(U$1-PF0-Pad10)") (class "Default")
      (node (ref "U$1") (pin "10") (pinfunction "PF0_10") (pintype "bidirectional"))
    )
    (net (code "70") (name "unconnected-(U$1-PF1-Pad11)") (class "Default")
      (node (ref "U$1") (pin "11") (pinfunction "PF1_11") (pintype "bidirectional"))
    )
    (net (code "71") (name "unconnected-(U$10-A2-Pad4)") (class "Default")
      (node (ref "U$10") (pin "4") (pinfunction "A2_4") (pintype "bidirectional"))
    )
    (net (code "72") (name "unconnected-(U$10-C2-Pad3)") (class "Default")
      (node (ref "U$10") (pin "3") (pinfunction "C2_3") (pintype "bidirectional"))
    )
    (net (code "73") (name "unconnected-(U$10-VO2-Pad6)") (class "Default")
      (node (ref "U$10") (pin "6") (pinfunction "VO2_6") (pintype "bidirectional"))
    )
    (net (code "74") (name "unconnected-(U$11-Pad1)") (class "Default")
      (node (ref "U$11") (pin "1") (pinfunction "1_1") (pintype "bidirectional"))
    )
    (net (code "75") (name "unconnected-(U$11-Pad2)") (class "Default")
      (node (ref "U$11") (pin "2") (pinfunction "2_2") (pintype "bidirectional"))
    )
    (net (code "76") (name "unconnected-(U$11-Pad3)") (class "Default")
      (node (ref "U$11") (pin "3") (pinfunction "3_3") (pintype "bidirectional"))
    )
  )
)
